# DC-DC_converter.net
KiCad netlist of a schematic drawn in EAGLE
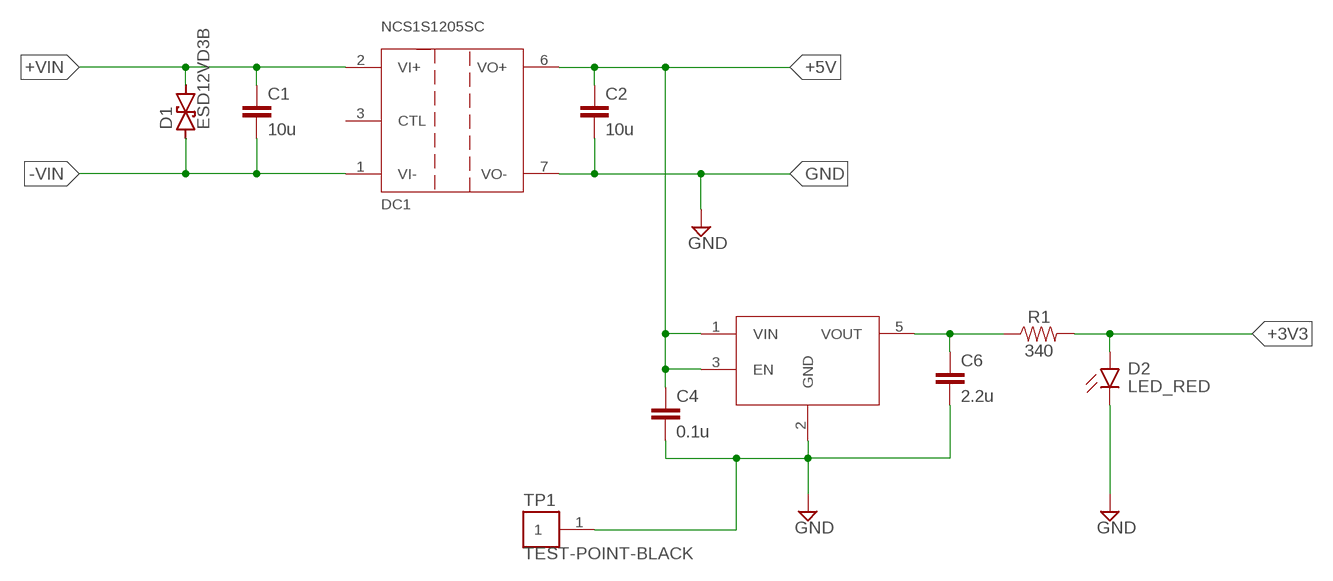
[diagram p0: schematic, sheet 1]

(export (version "E")
  (design (tool "Eeschema 10.0.6"))
  (components
    (comp (ref "C1")
      (value "10u")
      (footprint "eagle-import:1206")
      (fields (field (name "MFR") "Murata Electronics") (field (name "MPN") "GCM31CR71C106KA64K"))
      (libsource (lib "eagle-import") (part "CAP-10UF-10%-16V-X7R-1206IPC"))
    )
    (comp (ref "C2")
      (value "10u")
      (footprint "eagle-import:1206")
      (fields (field (name "MFR") "Murata Electronics") (field (name "MPN") "GCM31CR71C106KA64K"))
      (libsource (lib "eagle-import") (part "CAP-10UF-10%-16V-X7R-1206IPC"))
    )
    (comp (ref "C4")
      (value "0.1u")
      (footprint "eagle-import:C0603")
      (fields (field (name "MANUFACTURER") "Murata Electronics"))
      (libsource (lib "eagle-import") (part "CAP-0.1UF-0603-25V-X8R"))
    )
    (comp (ref "C6")
      (value "2.2u")
      (footprint "eagle-import:0603")
      (fields (field (name "MFR") "Murata Electronics") (field (name "MPN") "GCM188R70J225KE22D"))
      (libsource (lib "eagle-import") (part "CAP-2.2UF-10%-6.3V-X7R-0603IPC"))
    )
    (comp (ref "D1")
      (value "ESD12VD3B")
      (footprint "eagle-import:SOD23")
      (fields (field (name "MANUFACTURER") "Micro Commercial Co"))
      (libsource (lib "eagle-import") (part "ESD12VD3B"))
    )
    (comp (ref "D2")
      (value "LED_RED")
      (footprint "eagle-import:LEDC2012X110N_FLAT-R")
      (libsource (lib "eagle-import") (part "CHIP-FLAT-R_0805"))
    )
    (comp (ref "DC1")
      (value "NCS1S1205SC")
      (footprint "eagle-import:7-SIP")
      (fields (field (name "MANUFACTURER") "Murata"))
      (libsource (lib "eagle-import") (part "NCS1S1205SC"))
    )
    (comp (ref "DC2")
      (value "NCV551SN33T1G")
      (footprint "eagle-import:SOT23-5")
      (fields (field (name "MANUFACTURER") "ON Semiconductor"))
      (libsource (lib "eagle-import") (part "NCV551SN33T1G"))
    )
    (comp (ref "R1")
      (value "340")
      (footprint "eagle-import:R0603")
      (fields (field (name "MANUFACTURER") "Panasonic"))
      (libsource (lib "eagle-import") (part "RES-340OHM-0603-1/10W-1%"))
    )
    (comp (ref "TP1")
      (value "TEST-POINT-BLACK")
      (footprint "eagle-import:KEYSTONE_5001_0")
      (fields (field (name "MANUFACTURER") "Keystone Electronics"))
      (libsource (lib "eagle-import") (part "TEST-POINT-BLACK"))
    )
  )
  (nets
    (net (code "1") (name "+3V3") (class "Default")
      (node (ref "D2") (pin "A") (pinfunction "A_A") (pintype "passive"))
      (node (ref "R1") (pin "2") (pinfunction "2_2") (pintype "passive"))
    )
    (net (code "2") (name "+5V") (class "Default")
      (node (ref "C2") (pin "1") (pinfunction "1_1") (pintype "passive"))
      (node (ref "C4") (pin "1") (pinfunction "1_1") (pintype "passive"))
      (node (ref "DC1") (pin "6") (pinfunction "VO+_6") (pintype "power_in"))
      (node (ref "DC2") (pin "1") (pinfunction "VIN_1") (pintype "bidirectional"))
      (node (ref "DC2") (pin "3") (pinfunction "EN_3") (pintype "bidirectional"))
    )
    (net (code "3") (name "+VIN") (class "Default")
      (node (ref "C1") (pin "1") (pinfunction "1_1") (pintype "passive"))
      (node (ref "D1") (pin "2") (pinfunction "2_2") (pintype "passive"))
      (node (ref "DC1") (pin "2") (pinfunction "VI+_2") (pintype "power_in"))
    )
    (net (code "4") (name "-VIN") (class "Default")
      (node (ref "C1") (pin "2") (pinfunction "2_2") (pintype "passive"))
      (node (ref "D1") (pin "1") (pinfunction "1_1") (pintype "passive"))
      (node (ref "DC1") (pin "1") (pinfunction "VI-_1") (pintype "power_in"))
    )
    (net (code "5") (name "GND") (class "Default")
      (node (ref "C2") (pin "2") (pinfunction "2_2") (pintype "passive"))
      (node (ref "C4") (pin "2") (pinfunction "2_2") (pintype "passive"))
      (node (ref "C6") (pin "2") (pinfunction "2_2") (pintype "passive"))
      (node (ref "D2") (pin "C") (pinfunction "C_C") (pintype "passive"))
      (node (ref "DC1") (pin "7") (pinfunction "VO-_7") (pintype "power_in"))
      (node (ref "DC2") (pin "2") (pinfunction "GND_2") (pintype "bidirectional"))
      (node (ref "TP1") (pin "1") (pinfunction "1_1") (pintype "bidirectional"))
    )
    (net (code "6") (name "Net-(DC2-VOUT)") (class "Default")
      (node (ref "C6") (pin "1") (pinfunction "1_1") (pintype "passive"))
      (node (ref "DC2") (pin "5") (pinfunction "VOUT_5") (pintype "bidirectional"))
      (node (ref "R1") (pin "1") (pinfunction "1_1") (pintype "passive"))
    )
    (net (code "7") (name "unconnected-(DC1-CTL-Pad3)") (class "Default")
      (node (ref "DC1") (pin "3") (pinfunction "CTL_3") (pintype "input"))
    )
  )
)
